# breakout_da14580.net
KiCad netlist of a schematic drawn in EAGLE
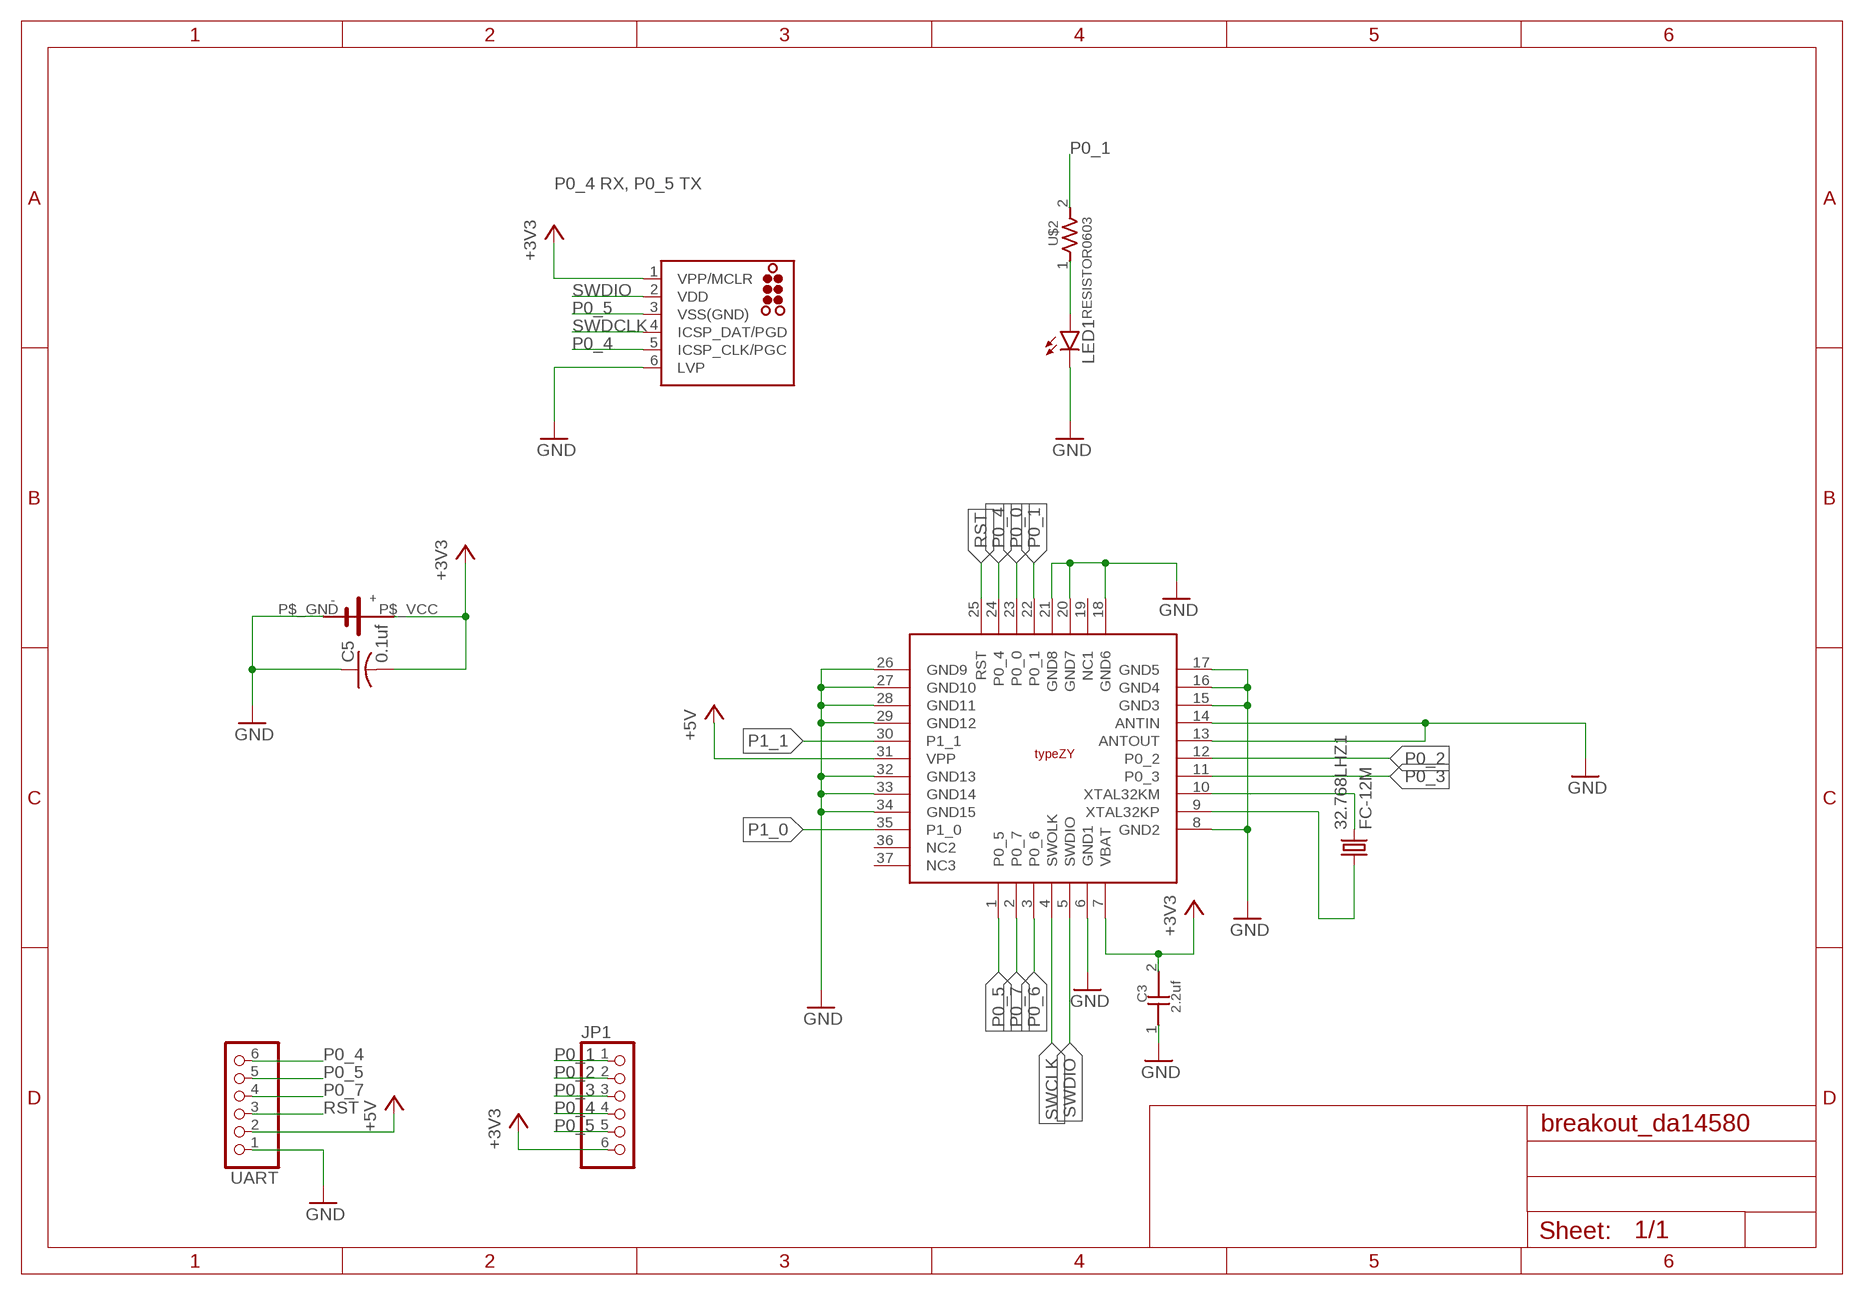
[diagram p0: schematic, sheet 1]

(export (version "E")
  (design (tool "Eeschema 10.0.6"))
  (components
    (comp (ref "32.768LHZ1")
      (value "FC-12M")
      (footprint "eagle-import:FC-12M")
      (libsource (lib "eagle-import") (part "FC-12M"))
    )
    (comp (ref "C3")
      (value "2.2uf")
      (footprint "eagle-import:0603")
      (libsource (lib "eagle-import") (part "CAPACITOR0603"))
    )
    (comp (ref "C5")
      (value "0.1uf")
      (footprint "eagle-import:C0603")
      (libsource (lib "eagle-import") (part "C-USC0603"))
    )
    (comp (ref "J1")
      (value "TC2030-MCP")
      (footprint "eagle-import:TC2030-MCP")
      (libsource (lib "eagle-import") (part "TC2030-MCP"))
    )
    (comp (ref "JP1")
      (value "PINHD-1X6")
      (footprint "eagle-import:1X06")
      (libsource (lib "eagle-import") (part "PINHD-1X6"))
    )
    (comp (ref "LED1")
      (value "LED-EIA0603")
      (footprint "eagle-import:EIA0603-LED")
      (libsource (lib "eagle-import") (part "LED-EIA0603"))
    )
    (comp (ref "U$1")
      (value "MURATA-TYPEZY")
      (footprint "eagle-import:MURATA_TYPEZY")
      (libsource (lib "eagle-import") (part "MURATA-TYPEZY"))
    )
    (comp (ref "U$2")
      (value "RESISTOR0603")
      (footprint "eagle-import:0603")
      (libsource (lib "eagle-import") (part "RESISTOR0603"))
    )
    (comp (ref "U$3")
      (value "SMTU2450-BOTTOM-MINI")
      (footprint "eagle-import:SMTU2450-BOTTOM-MINI")
      (libsource (lib "eagle-import") (part "SMTU2450-BOTTOM-MINI"))
    )
    (comp (ref "UART")
      (value "PINHD-1X6")
      (footprint "eagle-import:1X06")
      (libsource (lib "eagle-import") (part "PINHD-1X6"))
    )
  )
  (nets
    (net (code "1") (name "+3V3") (class "Default")
      (node (ref "C3") (pin "2") (pinfunction "2_2") (pintype "passive"))
      (node (ref "C5") (pin "2") (pinfunction "2_2") (pintype "passive"))
      (node (ref "J1") (pin "1") (pinfunction "VPP/MCLR_1") (pintype "passive"))
      (node (ref "JP1") (pin "6") (pinfunction "6_6") (pintype "passive"))
      (node (ref "U$1") (pin "7") (pinfunction "VBAT_7") (pintype "bidirectional"))
      (node (ref "U$3") (pin "P$_VCC") (pinfunction "P$_VCC_P$_VCC") (pintype "bidirectional"))
    )
    (net (code "2") (name "+5V") (class "Default")
      (node (ref "U$1") (pin "31") (pinfunction "VPP_31") (pintype "bidirectional"))
      (node (ref "UART") (pin "2") (pinfunction "2_2") (pintype "passive"))
    )
    (net (code "3") (name "/SWDCLK") (class "Default")
      (node (ref "J1") (pin "4") (pinfunction "ICSP_DAT/PGD_4") (pintype "bidirectional"))
    )
    (net (code "4") (name "GND") (class "Default")
      (node (ref "C3") (pin "1") (pinfunction "1_1") (pintype "passive"))
      (node (ref "C5") (pin "1") (pinfunction "1_1") (pintype "passive"))
      (node (ref "J1") (pin "6") (pinfunction "LVP_6") (pintype "bidirectional"))
      (node (ref "LED1") (pin "C") (pinfunction "C_C") (pintype "passive"))
      (node (ref "U$1") (pin "13") (pinfunction "ANTOUT_13") (pintype "bidirectional"))
      (node (ref "U$1") (pin "14") (pinfunction "ANTIN_14") (pintype "bidirectional"))
      (node (ref "U$1") (pin "15") (pinfunction "GND3_15") (pintype "bidirectional"))
      (node (ref "U$1") (pin "16") (pinfunction "GND4_16") (pintype "bidirectional"))
      (node (ref "U$1") (pin "17") (pinfunction "GND5_17") (pintype "bidirectional"))
      (node (ref "U$1") (pin "18") (pinfunction "GND6_18") (pintype "bidirectional"))
      (node (ref "U$1") (pin "20") (pinfunction "GND7_20") (pintype "bidirectional"))
      (node (ref "U$1") (pin "21") (pinfunction "GND8_21") (pintype "bidirectional"))
      (node (ref "U$1") (pin "26") (pinfunction "GND9_26") (pintype "bidirectional"))
      (node (ref "U$1") (pin "27") (pinfunction "GND10_27") (pintype "bidirectional"))
      (node (ref "U$1") (pin "28") (pinfunction "GND11_28") (pintype "bidirectional"))
      (node (ref "U$1") (pin "29") (pinfunction "GND12_29") (pintype "bidirectional"))
      (node (ref "U$1") (pin "32") (pinfunction "GND13_32") (pintype "bidirectional"))
      (node (ref "U$1") (pin "33") (pinfunction "GND14_33") (pintype "bidirectional"))
      (node (ref "U$1") (pin "34") (pinfunction "GND15_34") (pintype "bidirectional"))
      (node (ref "U$1") (pin "6") (pinfunction "GND1_6") (pintype "bidirectional"))
      (node (ref "U$1") (pin "8") (pinfunction "GND2_8") (pintype "bidirectional"))
      (node (ref "U$3") (pin "P$_GND") (pinfunction "P$_GND_P$_GND") (pintype "bidirectional"))
      (node (ref "UART") (pin "1") (pinfunction "1_1") (pintype "passive"))
    )
    (net (code "5") (name "Net-(LED1-PadA)") (class "Default")
      (node (ref "LED1") (pin "A") (pinfunction "A_A") (pintype "passive"))
      (node (ref "U$2") (pin "1") (pinfunction "1_1") (pintype "passive"))
    )
    (net (code "6") (name "Net-(U$1-XTAL32KM)") (class "Default")
      (node (ref "32.768LHZ1") (pin "2") (pinfunction "2_2") (pintype "passive"))
      (node (ref "U$1") (pin "10") (pinfunction "XTAL32KM_10") (pintype "bidirectional"))
    )
    (net (code "7") (name "Net-(U$1-XTAL32KP)") (class "Default")
      (node (ref "32.768LHZ1") (pin "1") (pinfunction "1_1") (pintype "passive"))
      (node (ref "U$1") (pin "9") (pinfunction "XTAL32KP_9") (pintype "bidirectional"))
    )
    (net (code "8") (name "P0_0") (class "Default")
      (node (ref "U$1") (pin "23") (pinfunction "P0_0_23") (pintype "bidirectional"))
    )
    (net (code "9") (name "P0_1") (class "Default")
      (node (ref "JP1") (pin "1") (pinfunction "1_1") (pintype "passive"))
      (node (ref "U$1") (pin "22") (pinfunction "P0_1_22") (pintype "bidirectional"))
      (node (ref "U$2") (pin "2") (pinfunction "2_2") (pintype "passive"))
    )
    (net (code "10") (name "P0_2") (class "Default")
      (node (ref "JP1") (pin "2") (pinfunction "2_2") (pintype "passive"))
      (node (ref "U$1") (pin "12") (pinfunction "P0_2_12") (pintype "bidirectional"))
    )
    (net (code "11") (name "P0_3") (class "Default")
      (node (ref "JP1") (pin "3") (pinfunction "3_3") (pintype "passive"))
      (node (ref "U$1") (pin "11") (pinfunction "P0_3_11") (pintype "bidirectional"))
    )
    (net (code "12") (name "P0_4") (class "Default")
      (node (ref "J1") (pin "5") (pinfunction "ICSP_CLK/PGC_5") (pintype "output"))
      (node (ref "JP1") (pin "4") (pinfunction "4_4") (pintype "passive"))
      (node (ref "U$1") (pin "24") (pinfunction "P0_4_24") (pintype "bidirectional"))
      (node (ref "UART") (pin "6") (pinfunction "6_6") (pintype "passive"))
    )
    (net (code "13") (name "P0_5") (class "Default")
      (node (ref "J1") (pin "3") (pinfunction "VSS(GND)_3") (pintype "power_in"))
      (node (ref "JP1") (pin "5") (pinfunction "5_5") (pintype "passive"))
      (node (ref "U$1") (pin "1") (pinfunction "P0_5_1") (pintype "bidirectional"))
      (node (ref "UART") (pin "5") (pinfunction "5_5") (pintype "passive"))
    )
    (net (code "14") (name "P0_6") (class "Default")
      (node (ref "U$1") (pin "3") (pinfunction "P0_6_3") (pintype "bidirectional"))
    )
    (net (code "15") (name "P0_7") (class "Default")
      (node (ref "U$1") (pin "2") (pinfunction "P0_7_2") (pintype "bidirectional"))
      (node (ref "UART") (pin "4") (pinfunction "4_4") (pintype "passive"))
    )
    (net (code "16") (name "P1_0") (class "Default")
      (node (ref "U$1") (pin "35") (pinfunction "P1_0_35") (pintype "bidirectional"))
    )
    (net (code "17") (name "P1_1") (class "Default")
      (node (ref "U$1") (pin "30") (pinfunction "P1_1_30") (pintype "bidirectional"))
    )
    (net (code "18") (name "RST") (class "Default")
      (node (ref "U$1") (pin "25") (pinfunction "RST_25") (pintype "bidirectional"))
      (node (ref "UART") (pin "3") (pinfunction "3_3") (pintype "passive"))
    )
    (net (code "19") (name "SWCLK") (class "Default")
      (node (ref "U$1") (pin "4") (pinfunction "SWOLK_4") (pintype "bidirectional"))
    )
    (net (code "20") (name "SWDIO") (class "Default")
      (node (ref "J1") (pin "2") (pinfunction "VDD_2") (pintype "power_in"))
      (node (ref "U$1") (pin "5") (pinfunction "SWDIO_5") (pintype "bidirectional"))
    )
    (net (code "21") (name "unconnected-(U$1-NC1-Pad19)") (class "Default")
      (node (ref "U$1") (pin "19") (pinfunction "NC1_19") (pintype "bidirectional"))
    )
    (net (code "22") (name "unconnected-(U$1-NC2-Pad36)") (class "Default")
      (node (ref "U$1") (pin "36") (pinfunction "NC2_36") (pintype "bidirectional"))
    )
    (net (code "23") (name "unconnected-(U$1-NC3-Pad37)") (class "Default")
      (node (ref "U$1") (pin "37") (pinfunction "NC3_37") (pintype "bidirectional"))
    )
  )
)
